# SensorTemperatura.net
KiCad netlist of a schematic drawn in Altium Designer
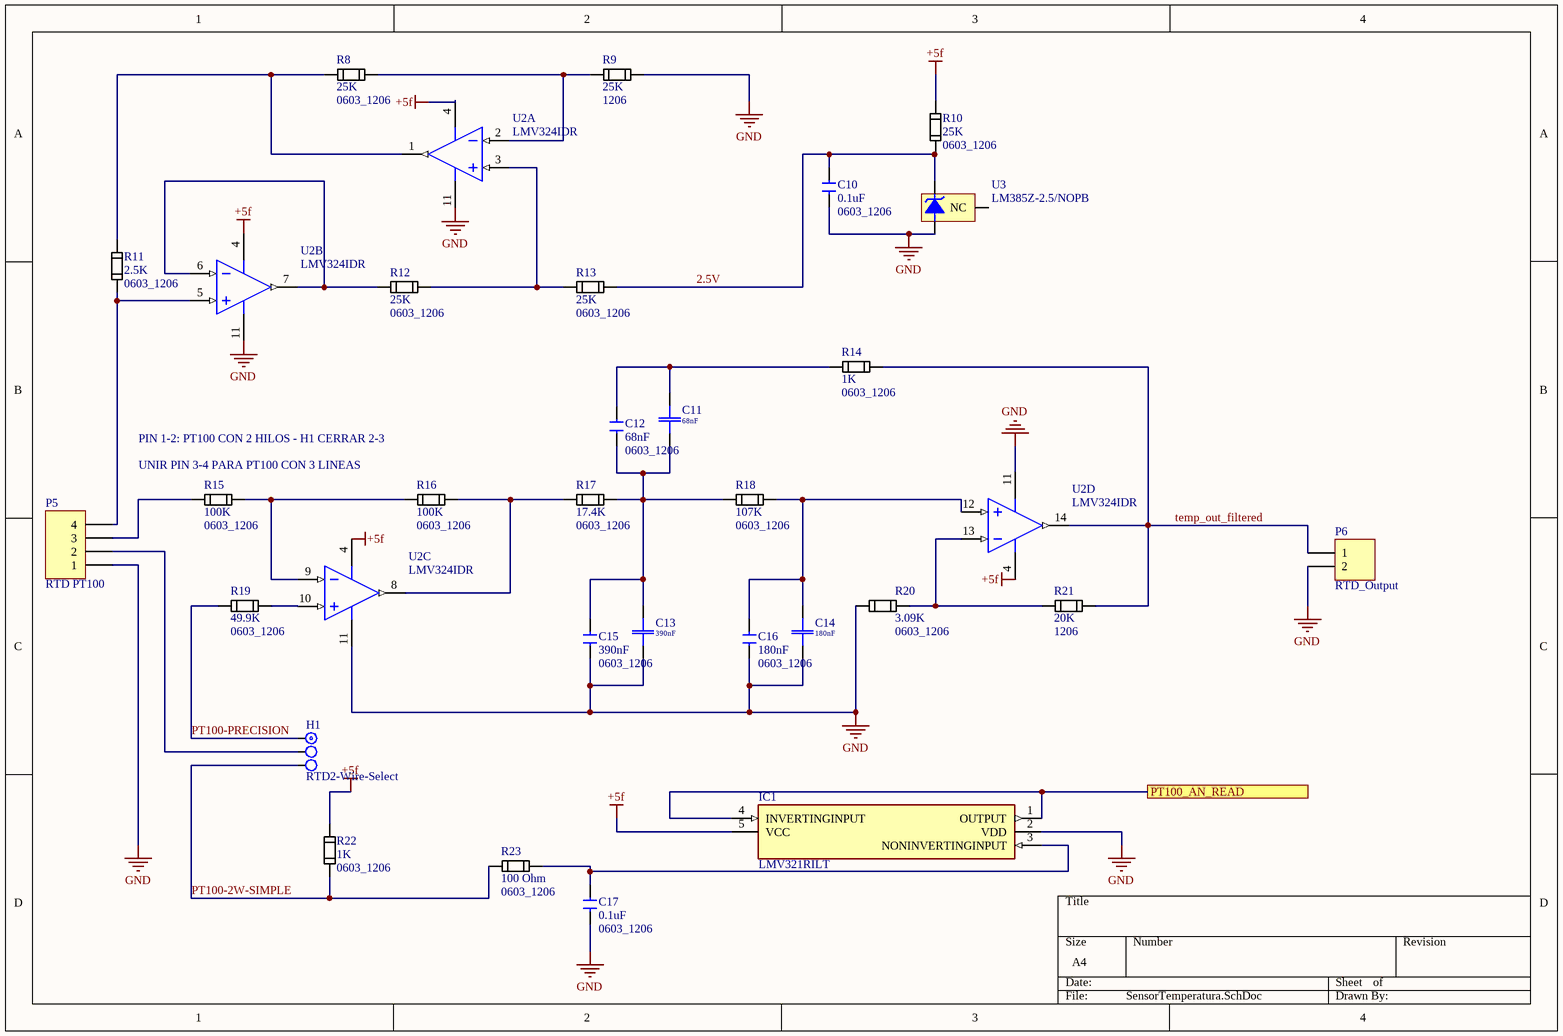
[diagram p0: SensorTemperatura.SchDoc]

(export (version "E")
  (design (tool "Eeschema 10.0.6"))
  (components
    (comp (ref "C10")
      (value "0.1uF")
      (footprint "SMD_CHIP_CAP_CER_0603_TO_1206")
      (description "SMD_CHIP_CAP_CER_0603_TO_1206")
      (fields (field (name "ALTIUM_VALUE") "0603_1206"))
      (libsource (lib "SMDCapacitors") (part "SMD_CHIP_CAP_CER_0603_TO_1206"))
    )
    (comp (ref "C11")
      (value "68nF")
      (footprint "Cap-Disk-D5.5-R5.08")
      (description "820p 1kV Y5P")
      (libsource (lib "Cap") (part "Cer Disc HV 820p 1kV"))
    )
    (comp (ref "C12")
      (value "68nF")
      (footprint "SMD_CHIP_CAP_CER_0603_TO_1206")
      (description "SMD_CHIP_CAP_CER_0603_TO_1206")
      (fields (field (name "ALTIUM_VALUE") "0603_1206"))
      (libsource (lib "SMDCapacitors") (part "SMD_CHIP_CAP_CER_0603_TO_1206"))
    )
    (comp (ref "C13")
      (value "390nF")
      (footprint "Cap-Disk-D5.5-R5.08")
      (description "820p 1kV Y5P")
      (libsource (lib "Cap") (part "Cer Disc HV 820p 1kV"))
    )
    (comp (ref "C14")
      (value "180nF")
      (footprint "Cap-Disk-D5.5-R5.08")
      (description "820p 1kV Y5P")
      (libsource (lib "Cap") (part "Cer Disc HV 820p 1kV"))
    )
    (comp (ref "C15")
      (value "390nF")
      (footprint "SMD_CHIP_CAP_CER_0603_TO_1206")
      (description "SMD_CHIP_CAP_CER_0603_TO_1206")
      (fields (field (name "ALTIUM_VALUE") "0603_1206"))
      (libsource (lib "SMDCapacitors") (part "SMD_CHIP_CAP_CER_0603_TO_1206"))
    )
    (comp (ref "C16")
      (value "180nF")
      (footprint "SMD_CHIP_CAP_CER_0603_TO_1206")
      (description "SMD_CHIP_CAP_CER_0603_TO_1206")
      (fields (field (name "ALTIUM_VALUE") "0603_1206"))
      (libsource (lib "SMDCapacitors") (part "SMD_CHIP_CAP_CER_0603_TO_1206"))
    )
    (comp (ref "C17")
      (value "0.1uF")
      (footprint "SMD_CHIP_CAP_CER_0603_TO_1206")
      (description "SMD_CHIP_CAP_CER_0603_TO_1206")
      (fields (field (name "ALTIUM_VALUE") "0603_1206"))
      (libsource (lib "SMDCapacitors") (part "SMD_CHIP_CAP_CER_0603_TO_1206"))
    )
    (comp (ref "H1")
      (value "RTD2-Wire-Select")
      (footprint "J1x3")
      (libsource (lib "Connektor") (part "H-1x3"))
    )
    (comp (ref "IC1")
      (value "LMV321RILT")
      (footprint "SamacSys:SOT95P280X145-5N")
      (description "Integrated Circuit")
      (fields (field (name "MOUSER PART NUMBER") "511-LMV321RILT") (field (name "RS PART NUMBER") "0426130P"))
      (libsource (lib "*") (part "LMV321RILT"))
    )
    (comp (ref "P5")
      (value "RTD PT100")
      (footprint "KF2EDGV/R-4P")
      (description "Header, 4-Pin")
      (fields (field (name "PUBLISHER") "Altium Limited"))
      (libsource (lib "Miscellaneous Connectors") (part "Header 4"))
    )
    (comp (ref "P6")
      (value "RTD_Output")
      (footprint "HDR1X2")
      (description "Header, 2-Pin")
      (fields (field (name "PUBLISHER") "Altium Limited"))
      (libsource (lib "Miscellaneous Connectors") (part "Header 2"))
    )
    (comp (ref "R8")
      (value "25K")
      (footprint "SMD_CHIP_RESISTOR_1206")
      (description "SMD_CHIP_RESISTOR_0603_TO_1206")
      (fields (field (name "ALTIUM_VALUE") "0603_1206"))
      (libsource (lib "SMDResistors") (part "SMD_CHIP_RESISTOR_0603_TO_1206"))
    )
    (comp (ref "R9")
      (value "25K")
      (footprint "SMD_CHIP_RESISTOR_1206")
      (description "SMD_CHIP_RESISTOR_1206")
      (fields (field (name "ALTIUM_VALUE") "1206"))
      (libsource (lib "SMDResistors") (part "SMD_CHIP_RESISTOR_1206"))
    )
    (comp (ref "R10")
      (value "25K")
      (footprint "SMD_CHIP_RESISTOR_0603_TO_1206")
      (description "SMD_CHIP_RESISTOR_0603_TO_1206")
      (fields (field (name "ALTIUM_VALUE") "0603_1206"))
      (libsource (lib "SMDResistors") (part "SMD_CHIP_RESISTOR_0603_TO_1206"))
    )
    (comp (ref "R11")
      (value "2.5K")
      (footprint "SMD_CHIP_RESISTOR_1206")
      (description "SMD_CHIP_RESISTOR_0603_TO_1206")
      (fields (field (name "ALTIUM_VALUE") "0603_1206"))
      (libsource (lib "SMDResistors") (part "SMD_CHIP_RESISTOR_0603_TO_1206"))
    )
    (comp (ref "R12")
      (value "25K")
      (footprint "SMD_CHIP_RESISTOR_1206")
      (description "SMD_CHIP_RESISTOR_0603_TO_1206")
      (fields (field (name "ALTIUM_VALUE") "0603_1206"))
      (libsource (lib "SMDResistors") (part "SMD_CHIP_RESISTOR_0603_TO_1206"))
    )
    (comp (ref "R13")
      (value "25K")
      (footprint "SMD_CHIP_RESISTOR_1206")
      (description "SMD_CHIP_RESISTOR_0603_TO_1206")
      (fields (field (name "ALTIUM_VALUE") "0603_1206"))
      (libsource (lib "SMDResistors") (part "SMD_CHIP_RESISTOR_0603_TO_1206"))
    )
    (comp (ref "R14")
      (value "1K")
      (footprint "SMD_CHIP_RESISTOR_0603_TO_1206")
      (description "SMD_CHIP_RESISTOR_0603_TO_1206")
      (fields (field (name "ALTIUM_VALUE") "0603_1206"))
      (libsource (lib "SMDResistors") (part "SMD_CHIP_RESISTOR_0603_TO_1206"))
    )
    (comp (ref "R15")
      (value "100K")
      (footprint "SMD_CHIP_RESISTOR_1206")
      (description "SMD_CHIP_RESISTOR_0603_TO_1206")
      (fields (field (name "ALTIUM_VALUE") "0603_1206"))
      (libsource (lib "SMDResistors") (part "SMD_CHIP_RESISTOR_0603_TO_1206"))
    )
    (comp (ref "R16")
      (value "100K")
      (footprint "SMD_CHIP_RESISTOR_1206")
      (description "SMD_CHIP_RESISTOR_0603_TO_1206")
      (fields (field (name "ALTIUM_VALUE") "0603_1206"))
      (libsource (lib "SMDResistors") (part "SMD_CHIP_RESISTOR_0603_TO_1206"))
    )
    (comp (ref "R17")
      (value "17.4K")
      (footprint "SMD_CHIP_RESISTOR_1206")
      (description "SMD_CHIP_RESISTOR_0603_TO_1206")
      (fields (field (name "ALTIUM_VALUE") "0603_1206"))
      (libsource (lib "SMDResistors") (part "SMD_CHIP_RESISTOR_0603_TO_1206"))
    )
    (comp (ref "R18")
      (value "107K")
      (footprint "SMD_CHIP_RESISTOR_1206")
      (description "SMD_CHIP_RESISTOR_0603_TO_1206")
      (fields (field (name "ALTIUM_VALUE") "0603_1206"))
      (libsource (lib "SMDResistors") (part "SMD_CHIP_RESISTOR_0603_TO_1206"))
    )
    (comp (ref "R19")
      (value "49.9K")
      (footprint "SMD_CHIP_RESISTOR_1206")
      (description "SMD_CHIP_RESISTOR_0603_TO_1206")
      (fields (field (name "ALTIUM_VALUE") "0603_1206"))
      (libsource (lib "SMDResistors") (part "SMD_CHIP_RESISTOR_0603_TO_1206"))
    )
    (comp (ref "R20")
      (value "3.09K")
      (footprint "SMD_CHIP_RESISTOR_1206")
      (description "SMD_CHIP_RESISTOR_0603_TO_1206")
      (fields (field (name "ALTIUM_VALUE") "0603_1206"))
      (libsource (lib "SMDResistors") (part "SMD_CHIP_RESISTOR_0603_TO_1206"))
    )
    (comp (ref "R21")
      (value "20K")
      (footprint "SMD_CHIP_RESISTOR_1206")
      (description "SMD_CHIP_RESISTOR_1206")
      (fields (field (name "ALTIUM_VALUE") "1206"))
      (libsource (lib "SMDResistors") (part "SMD_CHIP_RESISTOR_1206"))
    )
    (comp (ref "R22")
      (value "1K")
      (footprint "SMD_CHIP_RESISTOR_1206")
      (description "SMD_CHIP_RESISTOR_0603_TO_1206")
      (fields (field (name "ALTIUM_VALUE") "0603_1206"))
      (libsource (lib "SMDResistors") (part "SMD_CHIP_RESISTOR_0603_TO_1206"))
    )
    (comp (ref "R23")
      (value "100 Ohm")
      (footprint "SMD_CHIP_RESISTOR_1206")
      (description "SMD_CHIP_RESISTOR_0603_TO_1206")
      (fields (field (name "ALTIUM_VALUE") "0603_1206"))
      (libsource (lib "SMDResistors") (part "SMD_CHIP_RESISTOR_0603_TO_1206"))
    )
    (comp (ref "U2")
      (value "LMV324IDR")
      (footprint "D0014A_V")
      (libsource (lib "Altium Content Vault") (part "TI-LMV324-D-14"))
    )
    (comp (ref "U3")
      (value "LM385Z-2.5/NOPB")
      (footprint "Z03A")
      (description "Micropower Voltage Reference Diode, 3-pin TO-92, Pb-Free")
      (fields (field (name "MANUFACTURER") "National Semiconductor"))
      (libsource (lib "Altium Content Vault") (part "PM-REF-LM113-IL3A"))
    )
  )
  (nets
    (net (code "1") (name "+5f") (class "Default")
      (node (ref "IC1") (pin "5") (pinfunction "VCC_5") (pintype "power_in"))
      (node (ref "R10") (pin "2") (pinfunction "2_2") (pintype "passive"))
      (node (ref "R22") (pin "2") (pinfunction "2_2") (pintype "passive"))
      (node (ref "U2") (pin "4") (pinfunction "VCC+_4") (pintype "power_in"))
    )
    (net (code "2") (name "/2.5V") (class "Default")
      (node (ref "C10") (pin "2") (pinfunction "2_2") (pintype "passive"))
      (node (ref "R10") (pin "1") (pinfunction "1_1") (pintype "passive"))
      (node (ref "R13") (pin "2") (pinfunction "2_2") (pintype "passive"))
      (node (ref "U3") (pin "2") (pinfunction "+V_2") (pintype "passive"))
    )
    (net (code "3") (name "/PT100-2W-SIMPLE") (class "Default")
      (node (ref "H1") (pin "3") (pinfunction "3_3") (pintype "passive"))
      (node (ref "R22") (pin "1") (pinfunction "1_1") (pintype "passive"))
      (node (ref "R23") (pin "2") (pinfunction "2_2") (pintype "passive"))
    )
    (net (code "4") (name "/PT100-PRECISION") (class "Default")
      (node (ref "H1") (pin "1") (pinfunction "1_1") (pintype "passive"))
      (node (ref "R19") (pin "1") (pinfunction "1_1") (pintype "passive"))
    )
    (net (code "5") (name "/PT100_AN_READ") (class "Default")
      (node (ref "IC1") (pin "1") (pinfunction "OUTPUT_1") (pintype "output"))
      (node (ref "IC1") (pin "4") (pinfunction "INVERTINGINPUT_4") (pintype "input"))
    )
    (net (code "6") (name "/temp_out_filtered") (class "Default")
      (node (ref "P6") (pin "1") (pinfunction "1_1") (pintype "passive"))
      (node (ref "R14") (pin "2") (pinfunction "2_2") (pintype "passive"))
      (node (ref "R21") (pin "2") (pinfunction "2_2") (pintype "passive"))
      (node (ref "U2") (pin "14") (pinfunction "4OUT_14") (pintype "output"))
    )
    (net (code "7") (name "GND") (class "Default")
      (node (ref "C10") (pin "1") (pinfunction "1_1") (pintype "passive"))
      (node (ref "C13") (pin "2") (pinfunction "2_2") (pintype "passive"))
      (node (ref "C14") (pin "2") (pinfunction "2_2") (pintype "passive"))
      (node (ref "C15") (pin "1") (pinfunction "1_1") (pintype "passive"))
      (node (ref "C16") (pin "1") (pinfunction "1_1") (pintype "passive"))
      (node (ref "C17") (pin "1") (pinfunction "1_1") (pintype "passive"))
      (node (ref "IC1") (pin "2") (pinfunction "VDD_2") (pintype "power_in"))
      (node (ref "P5") (pin "1") (pinfunction "1_1") (pintype "passive"))
      (node (ref "P6") (pin "2") (pinfunction "2_2") (pintype "passive"))
      (node (ref "R20") (pin "1") (pinfunction "1_1") (pintype "passive"))
      (node (ref "R9") (pin "2") (pinfunction "2_2") (pintype "passive"))
      (node (ref "U2") (pin "11") (pinfunction "GND_11") (pintype "power_in"))
      (node (ref "U3") (pin "3") (pinfunction "-V_3") (pintype "passive"))
    )
    (net (code "8") (name "Net-(C11-Pad1)") (class "Default")
      (node (ref "C11") (pin "1") (pinfunction "1_1") (pintype "passive"))
      (node (ref "C12") (pin "2") (pinfunction "2_2") (pintype "passive"))
      (node (ref "R14") (pin "1") (pinfunction "1_1") (pintype "passive"))
    )
    (net (code "9") (name "Net-(C11-Pad2)") (class "Default")
      (node (ref "C11") (pin "2") (pinfunction "2_2") (pintype "passive"))
      (node (ref "C12") (pin "1") (pinfunction "1_1") (pintype "passive"))
      (node (ref "C13") (pin "1") (pinfunction "1_1") (pintype "passive"))
      (node (ref "C15") (pin "2") (pinfunction "2_2") (pintype "passive"))
      (node (ref "R17") (pin "2") (pinfunction "2_2") (pintype "passive"))
      (node (ref "R18") (pin "1") (pinfunction "1_1") (pintype "passive"))
    )
    (net (code "10") (name "Net-(H1-Pad2)") (class "Default")
      (node (ref "H1") (pin "2") (pinfunction "2_2") (pintype "passive"))
      (node (ref "P5") (pin "2") (pinfunction "2_2") (pintype "passive"))
    )
    (net (code "11") (name "Net-(IC1-NONINVERTINGINPUT)") (class "Default")
      (node (ref "C17") (pin "2") (pinfunction "2_2") (pintype "passive"))
      (node (ref "IC1") (pin "3") (pinfunction "NONINVERTINGINPUT_3") (pintype "input"))
      (node (ref "R23") (pin "1") (pinfunction "1_1") (pintype "passive"))
    )
    (net (code "12") (name "Net-(P5-Pad3)") (class "Default")
      (node (ref "P5") (pin "3") (pinfunction "3_3") (pintype "passive"))
      (node (ref "R15") (pin "1") (pinfunction "1_1") (pintype "passive"))
    )
    (net (code "13") (name "Net-(U2A-1IN+)") (class "Default")
      (node (ref "R12") (pin "2") (pinfunction "2_2") (pintype "passive"))
      (node (ref "R13") (pin "1") (pinfunction "1_1") (pintype "passive"))
      (node (ref "U2") (pin "3") (pinfunction "1IN+_3") (pintype "input"))
    )
    (net (code "14") (name "Net-(U2A-1IN-)") (class "Default")
      (node (ref "R8") (pin "2") (pinfunction "2_2") (pintype "passive"))
      (node (ref "R9") (pin "1") (pinfunction "1_1") (pintype "passive"))
      (node (ref "U2") (pin "2") (pinfunction "1IN-_2") (pintype "input"))
    )
    (net (code "15") (name "Net-(U2A-1OUT)") (class "Default")
      (node (ref "R11") (pin "2") (pinfunction "2_2") (pintype "passive"))
      (node (ref "R8") (pin "1") (pinfunction "1_1") (pintype "passive"))
      (node (ref "U2") (pin "1") (pinfunction "1OUT_1") (pintype "output"))
    )
    (net (code "16") (name "Net-(U2B-2IN+)") (class "Default")
      (node (ref "P5") (pin "4") (pinfunction "4_4") (pintype "passive"))
      (node (ref "R11") (pin "1") (pinfunction "1_1") (pintype "passive"))
      (node (ref "U2") (pin "5") (pinfunction "2IN+_5") (pintype "input"))
    )
    (net (code "17") (name "Net-(U2B-2IN-)") (class "Default")
      (node (ref "R12") (pin "1") (pinfunction "1_1") (pintype "passive"))
      (node (ref "U2") (pin "6") (pinfunction "2IN-_6") (pintype "input"))
      (node (ref "U2") (pin "7") (pinfunction "2OUT_7") (pintype "output"))
    )
    (net (code "18") (name "Net-(U2C-3IN+)") (class "Default")
      (node (ref "R19") (pin "2") (pinfunction "2_2") (pintype "passive"))
      (node (ref "U2") (pin "10") (pinfunction "3IN+_10") (pintype "input"))
    )
    (net (code "19") (name "Net-(U2C-3IN-)") (class "Default")
      (node (ref "R15") (pin "2") (pinfunction "2_2") (pintype "passive"))
      (node (ref "R16") (pin "1") (pinfunction "1_1") (pintype "passive"))
      (node (ref "U2") (pin "9") (pinfunction "3IN-_9") (pintype "input"))
    )
    (net (code "20") (name "Net-(U2C-3OUT)") (class "Default")
      (node (ref "R16") (pin "2") (pinfunction "2_2") (pintype "passive"))
      (node (ref "R17") (pin "1") (pinfunction "1_1") (pintype "passive"))
      (node (ref "U2") (pin "8") (pinfunction "3OUT_8") (pintype "output"))
    )
    (net (code "21") (name "Net-(U2D-4IN+)") (class "Default")
      (node (ref "C14") (pin "1") (pinfunction "1_1") (pintype "passive"))
      (node (ref "C16") (pin "2") (pinfunction "2_2") (pintype "passive"))
      (node (ref "R18") (pin "2") (pinfunction "2_2") (pintype "passive"))
      (node (ref "U2") (pin "12") (pinfunction "4IN+_12") (pintype "input"))
    )
    (net (code "22") (name "Net-(U2D-4IN-)") (class "Default")
      (node (ref "R20") (pin "2") (pinfunction "2_2") (pintype "passive"))
      (node (ref "R21") (pin "1") (pinfunction "1_1") (pintype "passive"))
      (node (ref "U2") (pin "13") (pinfunction "4IN-_13") (pintype "input"))
    )
    (net (code "23") (name "unconnected-(U3-NC-Pad1)") (class "Default")
      (node (ref "U3") (pin "1") (pinfunction "NC_1") (pintype "passive"))
    )
  )
)
